# connect.net
KiCad netlist of a schematic drawn in Altium Designer
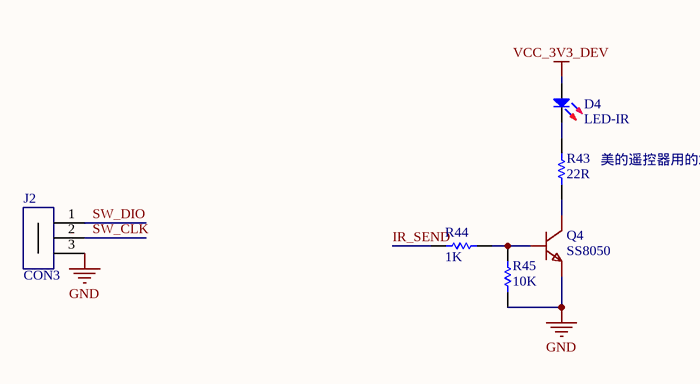
[diagram p0: connect.SchDoc]

(export (version "E")
  (design (tool "Eeschema 10.0.6"))
  (components
    (comp (ref "D4") (value "LED-IR") (footprint "IR12-21C") (libsource (lib "squ-guiboard") (part "LED-IR")))
    (comp (ref "J2") (value "CON3") (footprint "SMD_3P-1.25") (libsource (lib "Sheet") (part "CON3")))
    (comp (ref "Q4") (value "SS8050") (footprint "SOT-23") (libsource (lib "Sheet") (part "NPN")))
    (comp (ref "R43") (value "22R") (footprint "R 0603") (libsource (lib "Sheet") (part "RES")))
    (comp (ref "R44") (value "1K") (footprint "R 0603") (libsource (lib "Sheet") (part "RES")))
    (comp (ref "R45") (value "10K") (footprint "R 0603") (libsource (lib "Sheet") (part "RES")))
  )
  (nets
    (net (code "1") (name "/IR_SEND") (class "Default")
      (node (ref "R44") (pin "1") (pinfunction "1_1") (pintype "passive"))
    )
    (net (code "2") (name "/SW_CLK") (class "Default")
      (node (ref "J2") (pin "2") (pinfunction "2_2") (pintype "passive"))
    )
    (net (code "3") (name "/SW_DIO") (class "Default")
      (node (ref "J2") (pin "1") (pinfunction "1_1") (pintype "passive"))
    )
    (net (code "4") (name "GND") (class "Default")
      (node (ref "J2") (pin "3") (pinfunction "3_3") (pintype "passive"))
      (node (ref "Q4") (pin "2") (pinfunction "E_2") (pintype "passive"))
      (node (ref "R45") (pin "1") (pinfunction "1_1") (pintype "passive"))
    )
    (net (code "5") (name "Net-(D4-K)") (class "Default")
      (node (ref "D4") (pin "2") (pinfunction "K_2") (pintype "passive"))
      (node (ref "R43") (pin "2") (pinfunction "2_2") (pintype "passive"))
    )
    (net (code "6") (name "Net-(Q4-B)") (class "Default")
      (node (ref "Q4") (pin "1") (pinfunction "B_1") (pintype "passive"))
      (node (ref "R44") (pin "2") (pinfunction "2_2") (pintype "passive"))
      (node (ref "R45") (pin "2") (pinfunction "2_2") (pintype "passive"))
    )
    (net (code "7") (name "Net-(Q4-C)") (class "Default")
      (node (ref "Q4") (pin "3") (pinfunction "C_3") (pintype "passive"))
      (node (ref "R43") (pin "1") (pinfunction "1_1") (pintype "passive"))
    )
    (net (code "8") (name "VCC_3V3_DEV") (class "Default")
      (node (ref "D4") (pin "1") (pinfunction "A_1") (pintype "passive"))
    )
  )
)
